# schema3.net
KiCad netlist of a schematic drawn in Altium Designer
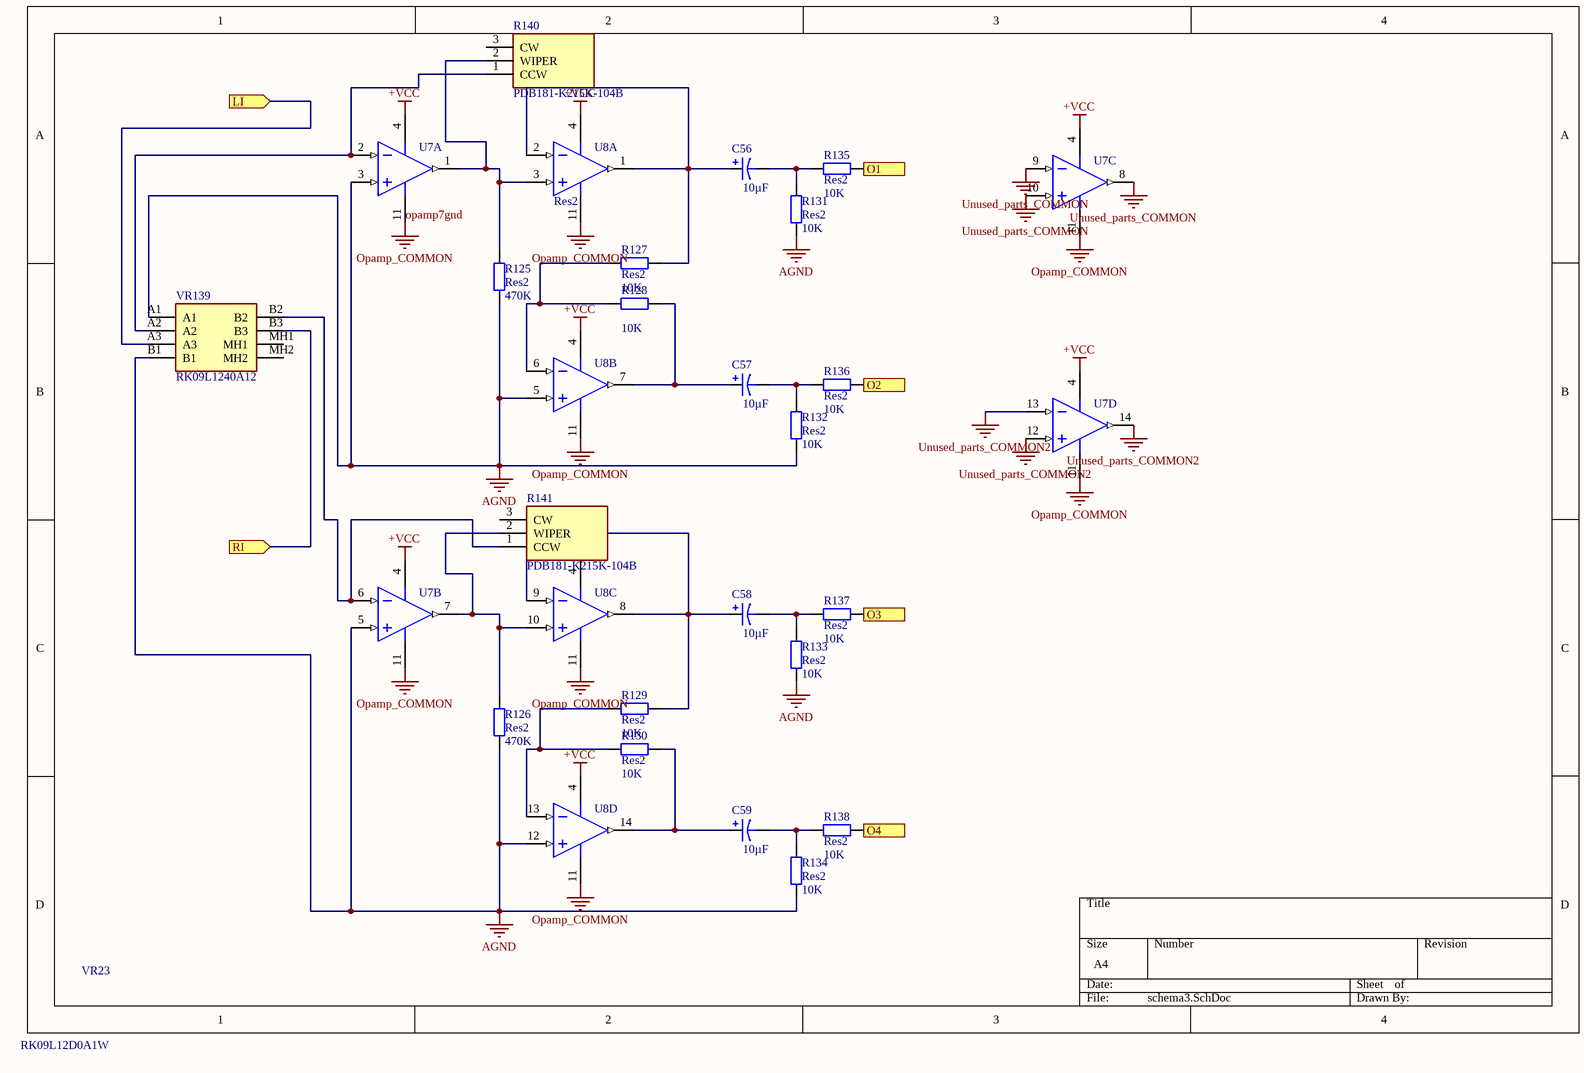
[diagram p0: schema3.SchDoc]

(export (version "E")
  (design (tool "Eeschema 10.0.6"))
  (components
    (comp (ref "C56")
      (value "10µF")
      (footprint "SMD_POLAR_CAPACITOR")
      (description "Polarized Capacitor (Radial)")
      (fields (field (name "Comment") "Cap Pol1") (field (name "PUBLISHER") "Altium Limited"))
      (libsource (lib "Miscellaneous Devices") (part "Cap Pol1"))
    )
    (comp (ref "C57")
      (value "10µF")
      (footprint "SMD_POLAR_CAPACITOR")
      (description "Polarized Capacitor (Radial)")
      (fields (field (name "Comment") "Cap Pol1") (field (name "PUBLISHER") "Altium Limited"))
      (libsource (lib "Miscellaneous Devices") (part "Cap Pol1"))
    )
    (comp (ref "C58")
      (value "10µF")
      (footprint "SMD_POLAR_CAPACITOR")
      (description "Polarized Capacitor (Radial)")
      (fields (field (name "Comment") "Cap Pol1") (field (name "PUBLISHER") "Altium Limited"))
      (libsource (lib "Miscellaneous Devices") (part "Cap Pol1"))
    )
    (comp (ref "C59")
      (value "10µF")
      (footprint "SMD_POLAR_CAPACITOR")
      (description "Polarized Capacitor (Radial)")
      (fields (field (name "Comment") "Cap Pol1") (field (name "PUBLISHER") "Altium Limited"))
      (libsource (lib "Miscellaneous Devices") (part "Cap Pol1"))
    )
    (comp (ref "R125")
      (value "Res2")
      (footprint "SMD_RESISTOR")
      (description "Resistor")
      (fields (field (name "ALTIUM_VALUE") "470K") (field (name "PUBLISHER") "Altium Limited"))
      (libsource (lib "Miscellaneous Devices") (part "Res2"))
    )
    (comp (ref "R126")
      (value "Res2")
      (footprint "SMD_RESISTOR")
      (description "Resistor")
      (fields (field (name "ALTIUM_VALUE") "470K") (field (name "PUBLISHER") "Altium Limited"))
      (libsource (lib "Miscellaneous Devices") (part "Res2"))
    )
    (comp (ref "R127")
      (value "Res2")
      (footprint "SMD_RESISTOR")
      (description "Resistor")
      (fields (field (name "ALTIUM_VALUE") "10K") (field (name "PUBLISHER") "Altium Limited"))
      (libsource (lib "") (part "Res2_1"))
    )
    (comp (ref "R128")
      (value "Res2")
      (footprint "SMD_RESISTOR")
      (description "Resistor")
      (fields (field (name "ALTIUM_VALUE") "10K") (field (name "PUBLISHER") "Altium Limited"))
      (libsource (lib "") (part "Res2_1"))
    )
    (comp (ref "R129")
      (value "Res2")
      (footprint "SMD_RESISTOR")
      (description "Resistor")
      (fields (field (name "ALTIUM_VALUE") "10K") (field (name "PUBLISHER") "Altium Limited"))
      (libsource (lib "") (part "Res2_1"))
    )
    (comp (ref "R130")
      (value "Res2")
      (footprint "SMD_RESISTOR")
      (description "Resistor")
      (fields (field (name "ALTIUM_VALUE") "10K") (field (name "PUBLISHER") "Altium Limited"))
      (libsource (lib "") (part "Res2_1"))
    )
    (comp (ref "R131")
      (value "Res2")
      (footprint "SMD_RESISTOR")
      (description "Resistor")
      (fields (field (name "ALTIUM_VALUE") "10K") (field (name "PUBLISHER") "Altium Limited"))
      (libsource (lib "Miscellaneous Devices") (part "Res2"))
    )
    (comp (ref "R132")
      (value "Res2")
      (footprint "SMD_RESISTOR")
      (description "Resistor")
      (fields (field (name "ALTIUM_VALUE") "10K") (field (name "PUBLISHER") "Altium Limited"))
      (libsource (lib "Miscellaneous Devices") (part "Res2"))
    )
    (comp (ref "R133")
      (value "Res2")
      (footprint "SMD_RESISTOR")
      (description "Resistor")
      (fields (field (name "ALTIUM_VALUE") "10K") (field (name "PUBLISHER") "Altium Limited"))
      (libsource (lib "Miscellaneous Devices") (part "Res2"))
    )
    (comp (ref "R134")
      (value "Res2")
      (footprint "SMD_RESISTOR")
      (description "Resistor")
      (fields (field (name "ALTIUM_VALUE") "10K") (field (name "PUBLISHER") "Altium Limited"))
      (libsource (lib "Miscellaneous Devices") (part "Res2"))
    )
    (comp (ref "R135")
      (value "Res2")
      (footprint "SMD_RESISTOR")
      (description "Resistor")
      (fields (field (name "ALTIUM_VALUE") "10K") (field (name "PUBLISHER") "Altium Limited"))
      (libsource (lib "") (part "Res2_1"))
    )
    (comp (ref "R136")
      (value "Res2")
      (footprint "SMD_RESISTOR")
      (description "Resistor")
      (fields (field (name "ALTIUM_VALUE") "10K") (field (name "PUBLISHER") "Altium Limited"))
      (libsource (lib "") (part "Res2_1"))
    )
    (comp (ref "R137")
      (value "Res2")
      (footprint "SMD_RESISTOR")
      (description "Resistor")
      (fields (field (name "ALTIUM_VALUE") "10K") (field (name "PUBLISHER") "Altium Limited"))
      (libsource (lib "") (part "Res2_1"))
    )
    (comp (ref "R138")
      (value "Res2")
      (footprint "SMD_RESISTOR")
      (description "Resistor")
      (fields (field (name "ALTIUM_VALUE") "10K") (field (name "PUBLISHER") "Altium Limited"))
      (libsource (lib "") (part "Res2_1"))
    )
    (comp (ref "R140")
      (value "PDB181-K215K-104B")
      (footprint "PcbLib1:PDB181K220K104B")
      (description "Variable Resistor")
      (libsource (lib "equalizer_project") (part "PDB181-K215K-104B"))
    )
    (comp (ref "R141")
      (value "PDB181-K215K-104B")
      (footprint "PcbLib1:PDB181K220K104B")
      (description "Variable Resistor")
      (libsource (lib "equalizer_project") (part "PDB181-K215K-104B"))
    )
    (comp (ref "U7")
      (value "OPA1664AIDR")
      (footprint "OPA1664AIDR")
      (fields (field (name "MANUFACTURER") "Texas Instruments"))
      (libsource (lib "equalizer_project") (part "CMP-0272-00211-3"))
    )
    (comp (ref "U8")
      (value "OPA1664AIDR")
      (footprint "OPA1664AIDR")
      (fields (field (name "MANUFACTURER") "Texas Instruments"))
      (libsource (lib "equalizer_project") (part "CMP-0272-00211-3"))
    )
    (comp (ref "VR23")
      (value "RK09L12D0A1W")
      (footprint "PcbLib1:RK09L12D0A1W")
      (description "Variable Resistor")
      (fields (field (name "MOUSER2 PART NUMBER") "688-RK09L12D0A1W"))
      (libsource (lib "*") (part "RK09L12D0A1W"))
    )
    (comp (ref "VR139")
      (value "RK09L1240A12")
      (footprint "RK09L124A12")
      (description "Variable Resistor")
      (fields (field (name "MOUSER2 PART NUMBER") "688-RK09L1240A12"))
      (libsource (lib "equalizer_project") (part "RK09L1240A12"))
    )
  )
  (nets
    (net (code "1") (name "+VCC") (class "Default")
      (node (ref "U7") (pin "4") (pinfunction "V+_4") (pintype "power_in"))
      (node (ref "U8") (pin "4") (pinfunction "V+_4") (pintype "power_in"))
    )
    (net (code "2") (name "/LI") (class "Default")
      (node (ref "VR139") (pin "A3") (pinfunction "A3_A3") (pintype "passive"))
    )
    (net (code "3") (name "/O1") (class "Default")
      (node (ref "R135") (pin "2") (pinfunction "2_2") (pintype "passive"))
    )
    (net (code "4") (name "/O2") (class "Default")
      (node (ref "R136") (pin "2") (pinfunction "2_2") (pintype "passive"))
    )
    (net (code "5") (name "/O3") (class "Default")
      (node (ref "R137") (pin "2") (pinfunction "2_2") (pintype "passive"))
    )
    (net (code "6") (name "/O4") (class "Default")
      (node (ref "R138") (pin "2") (pinfunction "2_2") (pintype "passive"))
    )
    (net (code "7") (name "/RI") (class "Default")
      (node (ref "VR139") (pin "B3") (pinfunction "B3_B3") (pintype "passive"))
    )
    (net (code "8") (name "AGND") (class "Default")
      (node (ref "R125") (pin "1") (pinfunction "1_1") (pintype "passive"))
      (node (ref "R126") (pin "1") (pinfunction "1_1") (pintype "passive"))
      (node (ref "R131") (pin "1") (pinfunction "1_1") (pintype "passive"))
      (node (ref "R132") (pin "1") (pinfunction "1_1") (pintype "passive"))
      (node (ref "R133") (pin "1") (pinfunction "1_1") (pintype "passive"))
      (node (ref "R134") (pin "1") (pinfunction "1_1") (pintype "passive"))
      (node (ref "U7") (pin "3") (pinfunction "IN_A+_3") (pintype "input"))
      (node (ref "U7") (pin "5") (pinfunction "IN_B+_5") (pintype "input"))
      (node (ref "U8") (pin "12") (pinfunction "IN_D+_12") (pintype "input"))
      (node (ref "U8") (pin "5") (pinfunction "IN_B+_5") (pintype "input"))
      (node (ref "VR139") (pin "A1") (pinfunction "A1_A1") (pintype "passive"))
      (node (ref "VR139") (pin "B1") (pinfunction "B1_B1") (pintype "passive"))
    )
    (net (code "9") (name "Net-(C56-Pad2)") (class "Default")
      (node (ref "C56") (pin "2") (pinfunction "2_2") (pintype "passive"))
      (node (ref "R131") (pin "2") (pinfunction "2_2") (pintype "passive"))
      (node (ref "R135") (pin "1") (pinfunction "1_1") (pintype "passive"))
    )
    (net (code "10") (name "Net-(C57-Pad2)") (class "Default")
      (node (ref "C57") (pin "2") (pinfunction "2_2") (pintype "passive"))
      (node (ref "R132") (pin "2") (pinfunction "2_2") (pintype "passive"))
      (node (ref "R136") (pin "1") (pinfunction "1_1") (pintype "passive"))
    )
    (net (code "11") (name "Net-(C58-Pad2)") (class "Default")
      (node (ref "C58") (pin "2") (pinfunction "2_2") (pintype "passive"))
      (node (ref "R133") (pin "2") (pinfunction "2_2") (pintype "passive"))
      (node (ref "R137") (pin "1") (pinfunction "1_1") (pintype "passive"))
    )
    (net (code "12") (name "Net-(C59-Pad2)") (class "Default")
      (node (ref "C59") (pin "2") (pinfunction "2_2") (pintype "passive"))
      (node (ref "R134") (pin "2") (pinfunction "2_2") (pintype "passive"))
      (node (ref "R138") (pin "1") (pinfunction "1_1") (pintype "passive"))
    )
    (net (code "13") (name "Net-(R140-CCW)") (class "Default")
      (node (ref "R140") (pin "1") (pinfunction "CCW_1") (pintype "passive"))
      (node (ref "U7") (pin "2") (pinfunction "IN_A-_2") (pintype "input"))
      (node (ref "VR139") (pin "A2") (pinfunction "A2_A2") (pintype "passive"))
    )
    (net (code "14") (name "Net-(R140-WIPER)") (class "Default")
      (node (ref "R125") (pin "2") (pinfunction "2_2") (pintype "passive"))
      (node (ref "R140") (pin "2") (pinfunction "WIPER_2") (pintype "passive"))
      (node (ref "U7") (pin "1") (pinfunction "OUT_A_1") (pintype "output"))
      (node (ref "U8") (pin "3") (pinfunction "IN_A+_3") (pintype "input"))
    )
    (net (code "15") (name "Net-(R141-CCW)") (class "Default")
      (node (ref "R141") (pin "1") (pinfunction "CCW_1") (pintype "passive"))
      (node (ref "U7") (pin "6") (pinfunction "IN_B-_6") (pintype "input"))
      (node (ref "VR139") (pin "B2") (pinfunction "B2_B2") (pintype "passive"))
    )
    (net (code "16") (name "Net-(R141-WIPER)") (class "Default")
      (node (ref "R126") (pin "2") (pinfunction "2_2") (pintype "passive"))
      (node (ref "R141") (pin "2") (pinfunction "WIPER_2") (pintype "passive"))
      (node (ref "U7") (pin "7") (pinfunction "OUT_B_7") (pintype "output"))
      (node (ref "U8") (pin "10") (pinfunction "IN_C+_10") (pintype "input"))
    )
    (net (code "17") (name "Net-(U8A-IN_A-)") (class "Default")
      (node (ref "C56") (pin "1") (pinfunction "1_1") (pintype "passive"))
      (node (ref "R127") (pin "2") (pinfunction "2_2") (pintype "passive"))
      (node (ref "U8") (pin "1") (pinfunction "OUT_A_1") (pintype "output"))
      (node (ref "U8") (pin "2") (pinfunction "IN_A-_2") (pintype "input"))
    )
    (net (code "18") (name "Net-(U8B-IN_B-)") (class "Default")
      (node (ref "R127") (pin "1") (pinfunction "1_1") (pintype "passive"))
      (node (ref "R128") (pin "1") (pinfunction "1_1") (pintype "passive"))
      (node (ref "U8") (pin "6") (pinfunction "IN_B-_6") (pintype "input"))
    )
    (net (code "19") (name "Net-(U8B-OUT_B)") (class "Default")
      (node (ref "C57") (pin "1") (pinfunction "1_1") (pintype "passive"))
      (node (ref "R128") (pin "2") (pinfunction "2_2") (pintype "passive"))
      (node (ref "U8") (pin "7") (pinfunction "OUT_B_7") (pintype "output"))
    )
    (net (code "20") (name "Net-(U8C-IN_C-)") (class "Default")
      (node (ref "C58") (pin "1") (pinfunction "1_1") (pintype "passive"))
      (node (ref "R129") (pin "2") (pinfunction "2_2") (pintype "passive"))
      (node (ref "U8") (pin "8") (pinfunction "OUT_C_8") (pintype "output"))
      (node (ref "U8") (pin "9") (pinfunction "IN_C-_9") (pintype "input"))
    )
    (net (code "21") (name "Net-(U8D-IN_D-)") (class "Default")
      (node (ref "R129") (pin "1") (pinfunction "1_1") (pintype "passive"))
      (node (ref "R130") (pin "1") (pinfunction "1_1") (pintype "passive"))
      (node (ref "U8") (pin "13") (pinfunction "IN_D-_13") (pintype "input"))
    )
    (net (code "22") (name "Net-(U8D-OUT_D)") (class "Default")
      (node (ref "C59") (pin "1") (pinfunction "1_1") (pintype "passive"))
      (node (ref "R130") (pin "2") (pinfunction "2_2") (pintype "passive"))
      (node (ref "U8") (pin "14") (pinfunction "OUT_D_14") (pintype "output"))
    )
    (net (code "23") (name "Opamp_COMMON") (class "Default")
      (node (ref "U7") (pin "11") (pinfunction "V-_11") (pintype "power_in"))
      (node (ref "U8") (pin "11") (pinfunction "V-_11") (pintype "power_in"))
    )
    (net (code "24") (name "Unused_parts_COMMON") (class "Default")
      (node (ref "U7") (pin "10") (pinfunction "IN_C+_10") (pintype "input"))
      (node (ref "U7") (pin "8") (pinfunction "OUT_C_8") (pintype "output"))
      (node (ref "U7") (pin "9") (pinfunction "IN_C-_9") (pintype "input"))
    )
    (net (code "25") (name "Unused_parts_COMMON2") (class "Default")
      (node (ref "U7") (pin "12") (pinfunction "IN_D+_12") (pintype "input"))
      (node (ref "U7") (pin "13") (pinfunction "IN_D-_13") (pintype "input"))
      (node (ref "U7") (pin "14") (pinfunction "OUT_D_14") (pintype "output"))
    )
    (net (code "26") (name "unconnected-(R140-CW-Pad3)") (class "Default")
      (node (ref "R140") (pin "3") (pinfunction "CW_3") (pintype "passive"))
    )
    (net (code "27") (name "unconnected-(R141-CW-Pad3)") (class "Default")
      (node (ref "R141") (pin "3") (pinfunction "CW_3") (pintype "passive"))
    )
    (net (code "28") (name "unconnected-(VR139-PadMH1)") (class "Default")
      (node (ref "VR139") (pin "MH1") (pinfunction "MH1_MH1") (pintype "passive"))
    )
    (net (code "29") (name "unconnected-(VR139-PadMH2)") (class "Default")
      (node (ref "VR139") (pin "MH2") (pinfunction "MH2_MH2") (pintype "passive"))
    )
  )
)
